# Power.net
KiCad netlist of a schematic drawn in Altium Designer
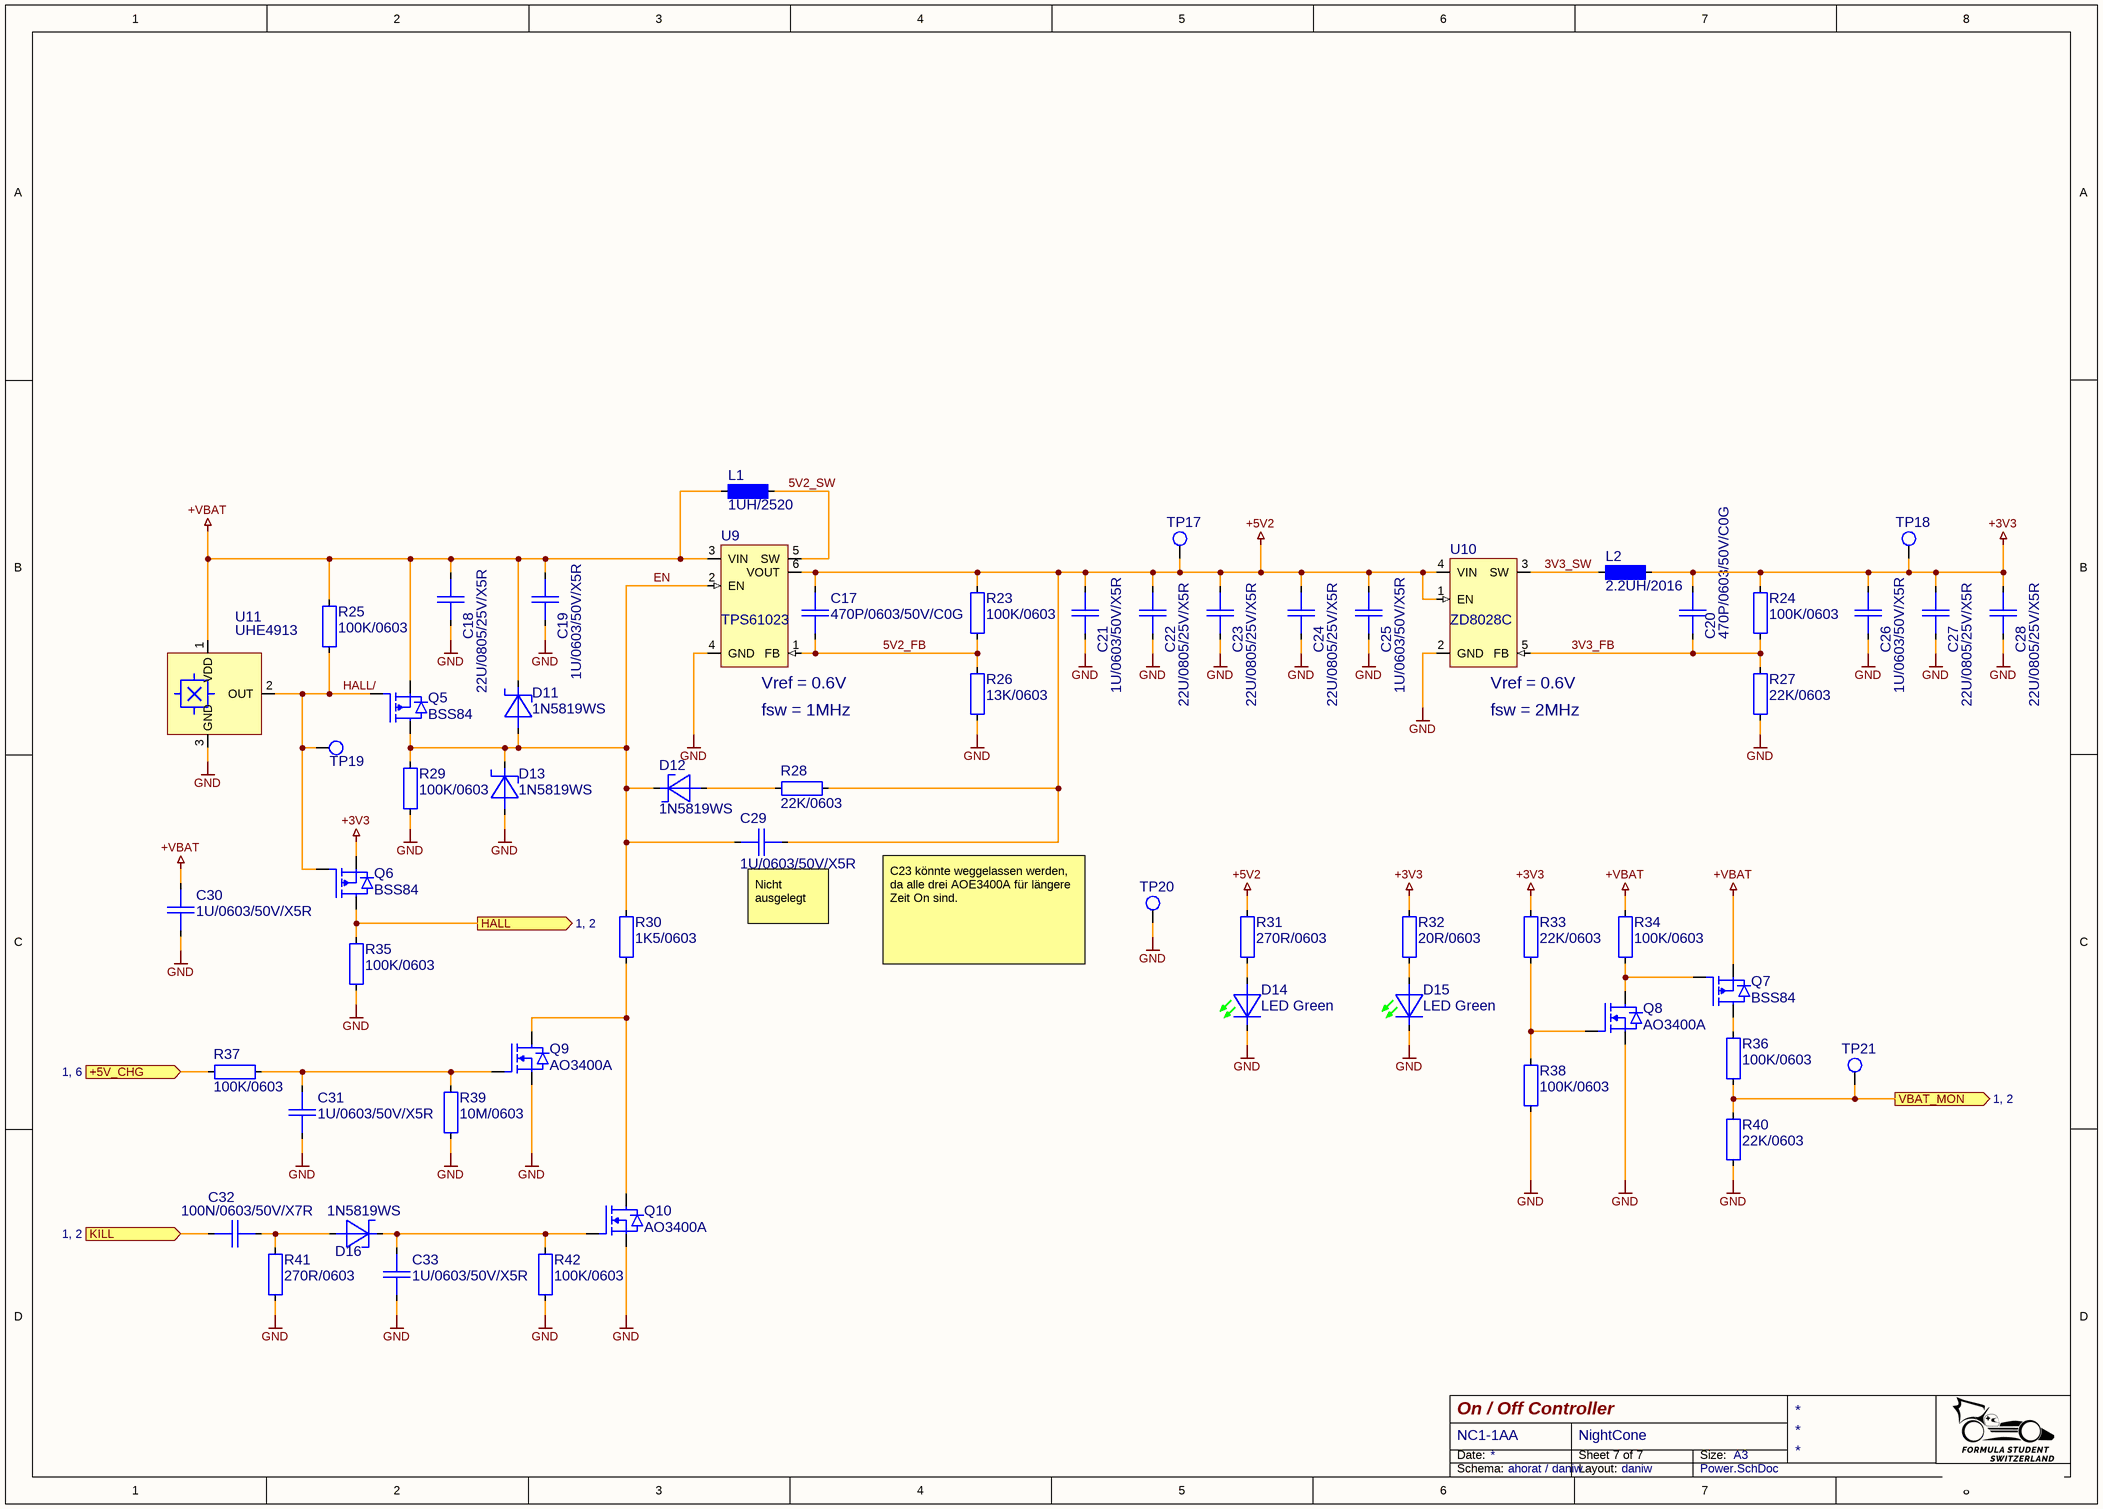
[diagram p0: Power.SchDoc]

(export (version "E")
  (design (tool "Eeschema 10.0.6"))
  (components
    (comp (ref "C17")
      (value "470P/0603/50V/C0G")
      (footprint "CAP0603_C0G")
      (description "CAP SM 0603 470pF 50V C0G")
      (fields (field (name "MANUFACTURER") "GENERIC"))
      (libsource (lib "daniw_altium_lib") (part "C"))
    )
    (comp (ref "C18")
      (value "22U/0805/25V/X5R")
      (footprint "CAP0805_X7R")
      (description "CAP SM 0805 22uF 25V X5R")
      (fields (field (name "MANUFACTURER") "GENERIC"))
      (libsource (lib "daniw_altium_lib") (part "C"))
    )
    (comp (ref "C19")
      (value "1U/0603/50V/X5R")
      (footprint "CAP0603_X7R")
      (description "CAP SM 0603 1.0uF 50V X5R")
      (fields (field (name "MANUFACTURER") "GENERIC"))
      (libsource (lib "daniw_altium_lib") (part "C"))
    )
    (comp (ref "C20")
      (value "470P/0603/50V/C0G")
      (footprint "CAP0603_C0G")
      (description "CAP SM 0603 470pF 50V C0G")
      (fields (field (name "MANUFACTURER") "GENERIC"))
      (libsource (lib "daniw_altium_lib") (part "C"))
    )
    (comp (ref "C21")
      (value "1U/0603/50V/X5R")
      (footprint "CAP0603_X7R")
      (description "CAP SM 0603 1.0uF 50V X5R")
      (fields (field (name "MANUFACTURER") "GENERIC"))
      (libsource (lib "daniw_altium_lib") (part "C"))
    )
    (comp (ref "C22")
      (value "22U/0805/25V/X5R")
      (footprint "CAP0805_X7R")
      (description "CAP SM 0805 22uF 25V X5R")
      (fields (field (name "MANUFACTURER") "GENERIC"))
      (libsource (lib "daniw_altium_lib") (part "C"))
    )
    (comp (ref "C23")
      (value "22U/0805/25V/X5R")
      (footprint "CAP0805_X7R")
      (description "CAP SM 0805 22uF 25V X5R")
      (fields (field (name "MANUFACTURER") "GENERIC"))
      (libsource (lib "daniw_altium_lib") (part "C"))
    )
    (comp (ref "C24")
      (value "22U/0805/25V/X5R")
      (footprint "CAP0805_X7R")
      (description "CAP SM 0805 22uF 25V X5R")
      (fields (field (name "MANUFACTURER") "GENERIC"))
      (libsource (lib "daniw_altium_lib") (part "C"))
    )
    (comp (ref "C25")
      (value "1U/0603/50V/X5R")
      (footprint "CAP0603_X7R")
      (description "CAP SM 0603 1.0uF 50V X5R")
      (fields (field (name "MANUFACTURER") "GENERIC"))
      (libsource (lib "daniw_altium_lib") (part "C"))
    )
    (comp (ref "C26")
      (value "1U/0603/50V/X5R")
      (footprint "CAP0603_X7R")
      (description "CAP SM 0603 1.0uF 50V X5R")
      (fields (field (name "MANUFACTURER") "GENERIC"))
      (libsource (lib "daniw_altium_lib") (part "C"))
    )
    (comp (ref "C27")
      (value "22U/0805/25V/X5R")
      (footprint "CAP0805_X7R")
      (description "CAP SM 0805 22uF 25V X5R")
      (fields (field (name "MANUFACTURER") "GENERIC"))
      (libsource (lib "daniw_altium_lib") (part "C"))
    )
    (comp (ref "C28")
      (value "22U/0805/25V/X5R")
      (footprint "CAP0805_X7R")
      (description "CAP SM 0805 22uF 25V X5R")
      (fields (field (name "MANUFACTURER") "GENERIC"))
      (libsource (lib "daniw_altium_lib") (part "C"))
    )
    (comp (ref "C29")
      (value "1U/0603/50V/X5R")
      (footprint "CAP0603_X7R")
      (description "CAP SM 0603 1.0uF 50V X5R")
      (fields (field (name "MANUFACTURER") "GENERIC"))
      (libsource (lib "daniw_altium_lib") (part "C"))
    )
    (comp (ref "C30")
      (value "1U/0603/50V/X5R")
      (footprint "CAP0603_X7R")
      (description "CAP SM 0603 1.0uF 50V X5R")
      (fields (field (name "MANUFACTURER") "GENERIC"))
      (libsource (lib "daniw_altium_lib") (part "C"))
    )
    (comp (ref "C31")
      (value "1U/0603/50V/X5R")
      (footprint "CAP0603_X7R")
      (description "CAP SM 0603 1.0uF 50V X5R")
      (fields (field (name "MANUFACTURER") "GENERIC"))
      (libsource (lib "daniw_altium_lib") (part "C"))
    )
    (comp (ref "C32")
      (value "100N/0603/50V/X7R")
      (footprint "CAP0603_X7R")
      (description "CAP SM 0603 100nF 50V X7R")
      (fields (field (name "MANUFACTURER") "GENERIC"))
      (libsource (lib "daniw_altium_lib") (part "C"))
    )
    (comp (ref "C33")
      (value "1U/0603/50V/X5R")
      (footprint "CAP0603_X7R")
      (description "CAP SM 0603 1.0uF 50V X5R")
      (fields (field (name "MANUFACTURER") "GENERIC"))
      (libsource (lib "daniw_altium_lib") (part "C"))
    )
    (comp (ref "D11")
      (value "1N5819WS")
      (footprint "SOD2513X100")
      (description "40V 600mV@1A 1A SOD-323 Schottky Barrier Diodes (SBD) ROHS")
      (fields (field (name "MANUFACTURER") "GENERIC"))
      (libsource (lib "daniw_altium_lib") (part "D_Schottky"))
    )
    (comp (ref "D12")
      (value "1N5819WS")
      (footprint "SOD2513X100")
      (description "40V 600mV@1A 1A SOD-323 Schottky Barrier Diodes (SBD) ROHS")
      (fields (field (name "MANUFACTURER") "GENERIC"))
      (libsource (lib "daniw_altium_lib") (part "D_Schottky"))
    )
    (comp (ref "D13")
      (value "1N5819WS")
      (footprint "SOD2513X100")
      (description "40V 600mV@1A 1A SOD-323 Schottky Barrier Diodes (SBD) ROHS")
      (fields (field (name "MANUFACTURER") "GENERIC"))
      (libsource (lib "daniw_altium_lib") (part "D_Schottky"))
    )
    (comp (ref "D14")
      (value "LED Green")
      (footprint "LED0805_GREEN")
      (description "Generic LED Green 0805")
      (fields (field (name "PART NUMBER") "LED Green 0805") (field (name "MANUFACTURER") "GENERIC"))
      (libsource (lib "daniw_altium_lib") (part "LED_GREEN"))
    )
    (comp (ref "D15")
      (value "LED Green")
      (footprint "LED0805_GREEN")
      (description "Generic LED Green 0805")
      (fields (field (name "PART NUMBER") "LED Green 0805") (field (name "MANUFACTURER") "GENERIC"))
      (libsource (lib "daniw_altium_lib") (part "LED_GREEN"))
    )
    (comp (ref "D16")
      (value "1N5819WS")
      (footprint "SOD2513X100")
      (description "40V 600mV@1A 1A SOD-323 Schottky Barrier Diodes (SBD) ROHS")
      (fields (field (name "MANUFACTURER") "GENERIC"))
      (libsource (lib "daniw_altium_lib") (part "D_Schottky"))
    )
    (comp (ref "L1")
      (value "1UH/2520")
      (footprint "INDM2520X10")
      (description "1UH 2520 Shielded Inductor SMD")
      (fields (field (name "MANUFACTURER") "GENERIC"))
      (libsource (lib "daniw_altium_lib") (part "L"))
    )
    (comp (ref "L2")
      (value "2.2UH/2016")
      (footprint "INDM2016X10")
      (description "2.2UH 2016 Shielded Inductor SMD")
      (fields (field (name "MANUFACTURER") "GENERIC"))
      (libsource (lib "daniw_altium_lib") (part "L"))
    )
    (comp (ref "Q5")
      (value "BSS84")
      (footprint "SOT2395P280X125-3-SE")
      (description "50V P-Channel MOSFET")
      (fields (field (name "MANUFACTURER") "GENERIC"))
      (libsource (lib "daniw_altium_lib") (part "MOSFET P_SOT23"))
    )
    (comp (ref "Q6")
      (value "BSS84")
      (footprint "SOT2395P280X125-3-SE")
      (description "50V P-Channel MOSFET")
      (fields (field (name "MANUFACTURER") "GENERIC"))
      (libsource (lib "daniw_altium_lib") (part "MOSFET P_SOT23"))
    )
    (comp (ref "Q7")
      (value "BSS84")
      (footprint "SOT2395P280X125-3-SE")
      (description "50V P-Channel MOSFET")
      (fields (field (name "MANUFACTURER") "GENERIC"))
      (libsource (lib "daniw_altium_lib") (part "MOSFET P_SOT23"))
    )
    (comp (ref "Q8")
      (value "AO3400A")
      (footprint "SOT2395P280X125-3-SE")
      (description "30V N-Channel MOSFET")
      (fields (field (name "MANUFACTURER") "Alpha & Omega Semiconductor"))
      (libsource (lib "daniw_altium_lib") (part "MOSFET N_SOT23"))
    )
    (comp (ref "Q9")
      (value "AO3400A")
      (footprint "SOT2395P280X125-3-SE")
      (description "30V N-Channel MOSFET")
      (fields (field (name "MANUFACTURER") "Alpha & Omega Semiconductor"))
      (libsource (lib "daniw_altium_lib") (part "MOSFET N_SOT23"))
    )
    (comp (ref "Q10")
      (value "AO3400A")
      (footprint "SOT2395P280X125-3-SE")
      (description "30V N-Channel MOSFET")
      (fields (field (name "MANUFACTURER") "Alpha & Omega Semiconductor"))
      (libsource (lib "daniw_altium_lib") (part "MOSFET N_SOT23"))
    )
    (comp (ref "R23")
      (value "100K/0603")
      (footprint "R0603-0.40-WW")
      (description "RES SM 0603 100K")
      (fields (field (name "MANUFACTURER") "GENERIC"))
      (libsource (lib "daniw_altium_lib") (part "R"))
    )
    (comp (ref "R24")
      (value "100K/0603")
      (footprint "R0603-0.40-WW")
      (description "RES SM 0603 100K")
      (fields (field (name "MANUFACTURER") "GENERIC"))
      (libsource (lib "daniw_altium_lib") (part "R"))
    )
    (comp (ref "R25")
      (value "100K/0603")
      (footprint "R0603-0.40-WW")
      (description "RES SM 0603 100K")
      (fields (field (name "MANUFACTURER") "GENERIC"))
      (libsource (lib "daniw_altium_lib") (part "R"))
    )
    (comp (ref "R26")
      (value "13K/0603")
      (footprint "R0603-0.40-WW")
      (description "RES SM 0603 13K")
      (fields (field (name "MANUFACTURER") "GENERIC"))
      (libsource (lib "daniw_altium_lib") (part "R"))
    )
    (comp (ref "R27")
      (value "22K/0603")
      (footprint "R0603-0.40-WW")
      (description "RES SM 0603 22K")
      (fields (field (name "MANUFACTURER") "GENERIC"))
      (libsource (lib "daniw_altium_lib") (part "R"))
    )
    (comp (ref "R28")
      (value "22K/0603")
      (footprint "R0603-0.40-WW")
      (description "RES SM 0603 22K")
      (fields (field (name "MANUFACTURER") "GENERIC"))
      (libsource (lib "daniw_altium_lib") (part "R"))
    )
    (comp (ref "R29")
      (value "100K/0603")
      (footprint "R0603-0.40-WW")
      (description "RES SM 0603 100K")
      (fields (field (name "MANUFACTURER") "GENERIC"))
      (libsource (lib "daniw_altium_lib") (part "R"))
    )
    (comp (ref "R30")
      (value "1K5/0603")
      (footprint "R0603-0.40-WW")
      (description "RES SM 0603 1K5")
      (fields (field (name "MANUFACTURER") "GENERIC"))
      (libsource (lib "daniw_altium_lib") (part "R"))
    )
    (comp (ref "R31")
      (value "270R/0603")
      (footprint "R0603-0.40-WW")
      (description "RES SM 0603 270R")
      (fields (field (name "MANUFACTURER") "GENERIC"))
      (libsource (lib "daniw_altium_lib") (part "R"))
    )
    (comp (ref "R32")
      (value "20R/0603")
      (footprint "R0603-0.40-WW")
      (description "RES SM 0603 20R")
      (fields (field (name "MANUFACTURER") "GENERIC"))
      (libsource (lib "daniw_altium_lib") (part "R"))
    )
    (comp (ref "R33")
      (value "22K/0603")
      (footprint "R0603-0.40-WW")
      (description "RES SM 0603 22K")
      (fields (field (name "MANUFACTURER") "GENERIC"))
      (libsource (lib "daniw_altium_lib") (part "R"))
    )
    (comp (ref "R34")
      (value "100K/0603")
      (footprint "R0603-0.40-WW")
      (description "RES SM 0603 100K")
      (fields (field (name "MANUFACTURER") "GENERIC"))
      (libsource (lib "daniw_altium_lib") (part "R"))
    )
    (comp (ref "R35")
      (value "100K/0603")
      (footprint "R0603-0.40-WW")
      (description "RES SM 0603 100K")
      (fields (field (name "MANUFACTURER") "GENERIC"))
      (libsource (lib "daniw_altium_lib") (part "R"))
    )
    (comp (ref "R36")
      (value "100K/0603")
      (footprint "R0603-0.40-WW")
      (description "RES SM 0603 100K")
      (fields (field (name "MANUFACTURER") "GENERIC"))
      (libsource (lib "daniw_altium_lib") (part "R"))
    )
    (comp (ref "R37")
      (value "100K/0603")
      (footprint "R0603-0.40-WW")
      (description "RES SM 0603 100K")
      (fields (field (name "MANUFACTURER") "GENERIC"))
      (libsource (lib "daniw_altium_lib") (part "R"))
    )
    (comp (ref "R38")
      (value "100K/0603")
      (footprint "R0603-0.40-WW")
      (description "RES SM 0603 100K")
      (fields (field (name "MANUFACTURER") "GENERIC"))
      (libsource (lib "daniw_altium_lib") (part "R"))
    )
    (comp (ref "R39")
      (value "10M/0603")
      (footprint "R0603-0.40-WW")
      (description "RES SM 0603 10M")
      (fields (field (name "MANUFACTURER") "GENERIC"))
      (libsource (lib "daniw_altium_lib") (part "R"))
    )
    (comp (ref "R40")
      (value "22K/0603")
      (footprint "R0603-0.40-WW")
      (description "RES SM 0603 22K")
      (fields (field (name "MANUFACTURER") "GENERIC"))
      (libsource (lib "daniw_altium_lib") (part "R"))
    )
    (comp (ref "R41")
      (value "270R/0603")
      (footprint "R0603-0.40-WW")
      (description "RES SM 0603 270R")
      (fields (field (name "MANUFACTURER") "GENERIC"))
      (libsource (lib "daniw_altium_lib") (part "R"))
    )
    (comp (ref "R42")
      (value "100K/0603")
      (footprint "R0603-0.40-WW")
      (description "RES SM 0603 100K")
      (fields (field (name "MANUFACTURER") "GENERIC"))
      (libsource (lib "daniw_altium_lib") (part "R"))
    )
    (comp (ref "TP17")
      (value "TP_THD_1.5/0.8")
      (footprint "TP_THD_1.5/0.8")
      (description "THT Test Point 1.5/0.8mm")
      (fields (field (name "MANUFACTURER") "NONE"))
      (libsource (lib "daniw_altium_lib") (part "Testpoint"))
    )
    (comp (ref "TP18")
      (value "TP_THD_1.5/0.8")
      (footprint "TP_THD_1.5/0.8")
      (description "THT Test Point 1.5/0.8mm")
      (fields (field (name "MANUFACTURER") "NONE"))
      (libsource (lib "daniw_altium_lib") (part "Testpoint"))
    )
    (comp (ref "TP19")
      (value "TP_THD_1.5/0.8")
      (footprint "TP_THD_1.5/0.8")
      (description "THT Test Point 1.5/0.8mm")
      (fields (field (name "MANUFACTURER") "NONE"))
      (libsource (lib "daniw_altium_lib") (part "Testpoint"))
    )
    (comp (ref "TP20")
      (value "TP_THD_1.5/0.8")
      (footprint "TP_THD_1.5/0.8")
      (description "THT Test Point 1.5/0.8mm")
      (fields (field (name "MANUFACTURER") "NONE"))
      (libsource (lib "daniw_altium_lib") (part "Testpoint"))
    )
    (comp (ref "TP21")
      (value "TP_THD_1.5/0.8")
      (footprint "TP_THD_1.5/0.8")
      (description "THT Test Point 1.5/0.8mm")
      (fields (field (name "MANUFACTURER") "NONE"))
      (libsource (lib "daniw_altium_lib") (part "Testpoint"))
    )
    (comp (ref "U9")
      (value "TPS61023")
      (footprint "SOT50P160X60-6-SE")
      (description "3.7-A Boost Converter with 0.5-V Ultra-low Input Voltage")
      (fields (field (name "MANUFACTURER") "Texas Instruments"))
      (libsource (lib "daniw_altium_lib") (part "TPS61023"))
    )
    (comp (ref "U10")
      (value "ZD8028C")
      (footprint "SOT2395P280X125-5-SW")
      (description "1.5A 2MHz 5.5V Synchronous Buck Converter")
      (fields (field (name "MANUFACTURER") "Zetta"))
      (libsource (lib "daniw_altium_lib") (part "ZD8028C"))
    )
    (comp (ref "U11")
      (value "UHE4913")
      (footprint "SOT2395P280X125-3-SE")
      (description "Ultra Low Power Hall Switch Open Drain")
      (fields (field (name "MANUFACTURER") "UTC(Unisonic Tech)"))
      (libsource (lib "daniw_altium_lib") (part "UHE4913"))
    )
  )
  (nets
    (net (code "1") (name "+3V3") (class "Default")
      (node (ref "C20") (pin "1") (pinfunction "1_1") (pintype "passive"))
      (node (ref "C26") (pin "2") (pinfunction "2_2") (pintype "passive"))
      (node (ref "C27") (pin "1") (pinfunction "1_1") (pintype "passive"))
      (node (ref "C28") (pin "1") (pinfunction "1_1") (pintype "passive"))
      (node (ref "L2") (pin "2") (pinfunction "2_2") (pintype "passive"))
      (node (ref "Q6") (pin "2") (pinfunction "SOURCE_2") (pintype "passive"))
      (node (ref "R24") (pin "1") (pinfunction "1_1") (pintype "passive"))
      (node (ref "R32") (pin "1") (pinfunction "1_1") (pintype "passive"))
      (node (ref "R33") (pin "1") (pinfunction "1_1") (pintype "passive"))
      (node (ref "TP18") (pin "1") (pinfunction "1_1") (pintype "passive"))
    )
    (net (code "2") (name "+5V2") (class "Default")
      (node (ref "C17") (pin "1") (pinfunction "1_1") (pintype "passive"))
      (node (ref "C21") (pin "2") (pinfunction "2_2") (pintype "passive"))
      (node (ref "C22") (pin "1") (pinfunction "1_1") (pintype "passive"))
      (node (ref "C23") (pin "1") (pinfunction "1_1") (pintype "passive"))
      (node (ref "C24") (pin "1") (pinfunction "1_1") (pintype "passive"))
      (node (ref "C25") (pin "2") (pinfunction "2_2") (pintype "passive"))
      (node (ref "C29") (pin "2") (pinfunction "2_2") (pintype "passive"))
      (node (ref "R23") (pin "1") (pinfunction "1_1") (pintype "passive"))
      (node (ref "R28") (pin "2") (pinfunction "2_2") (pintype "passive"))
      (node (ref "R31") (pin "1") (pinfunction "1_1") (pintype "passive"))
      (node (ref "TP17") (pin "1") (pinfunction "1_1") (pintype "passive"))
      (node (ref "U10") (pin "1") (pinfunction "EN_1") (pintype "input"))
      (node (ref "U10") (pin "4") (pinfunction "VIN_4") (pintype "passive"))
      (node (ref "U9") (pin "6") (pinfunction "VOUT_6") (pintype "passive"))
    )
    (net (code "3") (name "+VBAT") (class "Default")
      (node (ref "C18") (pin "1") (pinfunction "1_1") (pintype "passive"))
      (node (ref "C19") (pin "2") (pinfunction "2_2") (pintype "passive"))
      (node (ref "C30") (pin "1") (pinfunction "1_1") (pintype "passive"))
      (node (ref "D11") (pin "1") (pinfunction "1_1") (pintype "passive"))
      (node (ref "L1") (pin "1") (pinfunction "1_1") (pintype "passive"))
      (node (ref "Q5") (pin "2") (pinfunction "SOURCE_2") (pintype "passive"))
      (node (ref "Q7") (pin "2") (pinfunction "SOURCE_2") (pintype "passive"))
      (node (ref "R25") (pin "1") (pinfunction "1_1") (pintype "passive"))
      (node (ref "R34") (pin "1") (pinfunction "1_1") (pintype "passive"))
      (node (ref "U11") (pin "1") (pinfunction "VDD_1") (pintype "passive"))
      (node (ref "U9") (pin "3") (pinfunction "VIN_3") (pintype "passive"))
    )
    (net (code "4") (name "/+5V_CHG") (class "Default")
      (node (ref "R37") (pin "1") (pinfunction "1_1") (pintype "passive"))
    )
    (net (code "5") (name "/3V3_FB") (class "Default")
      (node (ref "C20") (pin "2") (pinfunction "2_2") (pintype "passive"))
      (node (ref "R24") (pin "2") (pinfunction "2_2") (pintype "passive"))
      (node (ref "R27") (pin "1") (pinfunction "1_1") (pintype "passive"))
      (node (ref "U10") (pin "5") (pinfunction "FB_5") (pintype "input"))
    )
    (net (code "6") (name "/3V3_SW") (class "Default")
      (node (ref "L2") (pin "1") (pinfunction "1_1") (pintype "passive"))
      (node (ref "U10") (pin "3") (pinfunction "SW_3") (pintype "passive"))
    )
    (net (code "7") (name "/5V2_FB") (class "Default")
      (node (ref "C17") (pin "2") (pinfunction "2_2") (pintype "passive"))
      (node (ref "R23") (pin "2") (pinfunction "2_2") (pintype "passive"))
      (node (ref "R26") (pin "2") (pinfunction "2_2") (pintype "passive"))
      (node (ref "U9") (pin "1") (pinfunction "FB_1") (pintype "input"))
    )
    (net (code "8") (name "/5V2_SW") (class "Default")
      (node (ref "L1") (pin "2") (pinfunction "2_2") (pintype "passive"))
      (node (ref "U9") (pin "5") (pinfunction "SW_5") (pintype "passive"))
    )
    (net (code "9") (name "/EN") (class "Default")
      (node (ref "C29") (pin "1") (pinfunction "1_1") (pintype "passive"))
      (node (ref "D11") (pin "2") (pinfunction "2_2") (pintype "passive"))
      (node (ref "D12") (pin "1") (pinfunction "1_1") (pintype "passive"))
      (node (ref "D13") (pin "1") (pinfunction "1_1") (pintype "passive"))
      (node (ref "Q5") (pin "3") (pinfunction "DRAIN_3") (pintype "passive"))
      (node (ref "R29") (pin "1") (pinfunction "1_1") (pintype "passive"))
      (node (ref "R30") (pin "1") (pinfunction "1_1") (pintype "passive"))
      (node (ref "U9") (pin "2") (pinfunction "EN_2") (pintype "input"))
    )
    (net (code "10") (name "/HALL") (class "Default")
      (node (ref "Q6") (pin "3") (pinfunction "DRAIN_3") (pintype "passive"))
      (node (ref "R35") (pin "1") (pinfunction "1_1") (pintype "passive"))
    )
    (net (code "11") (name "/HALL{slash}") (class "Default")
      (node (ref "Q5") (pin "1") (pinfunction "GATE_1") (pintype "passive"))
      (node (ref "Q6") (pin "1") (pinfunction "GATE_1") (pintype "passive"))
      (node (ref "R25") (pin "2") (pinfunction "2_2") (pintype "passive"))
      (node (ref "TP19") (pin "1") (pinfunction "1_1") (pintype "passive"))
      (node (ref "U11") (pin "2") (pinfunction "OUT_2") (pintype "open_collector"))
    )
    (net (code "12") (name "/KILL") (class "Default")
      (node (ref "C32") (pin "1") (pinfunction "1_1") (pintype "passive"))
    )
    (net (code "13") (name "/VBAT_MON") (class "Default")
      (node (ref "R36") (pin "2") (pinfunction "2_2") (pintype "passive"))
      (node (ref "R40") (pin "1") (pinfunction "1_1") (pintype "passive"))
      (node (ref "TP21") (pin "1") (pinfunction "1_1") (pintype "passive"))
    )
    (net (code "14") (name "GND") (class "Default")
      (node (ref "C18") (pin "2") (pinfunction "2_2") (pintype "passive"))
      (node (ref "C19") (pin "1") (pinfunction "1_1") (pintype "passive"))
      (node (ref "C21") (pin "1") (pinfunction "1_1") (pintype "passive"))
      (node (ref "C22") (pin "2") (pinfunction "2_2") (pintype "passive"))
      (node (ref "C23") (pin "2") (pinfunction "2_2") (pintype "passive"))
      (node (ref "C24") (pin "2") (pinfunction "2_2") (pintype "passive"))
      (node (ref "C25") (pin "1") (pinfunction "1_1") (pintype "passive"))
      (node (ref "C26") (pin "1") (pinfunction "1_1") (pintype "passive"))
      (node (ref "C27") (pin "2") (pinfunction "2_2") (pintype "passive"))
      (node (ref "C28") (pin "2") (pinfunction "2_2") (pintype "passive"))
      (node (ref "C30") (pin "2") (pinfunction "2_2") (pintype "passive"))
      (node (ref "C31") (pin "2") (pinfunction "2_2") (pintype "passive"))
      (node (ref "C33") (pin "2") (pinfunction "2_2") (pintype "passive"))
      (node (ref "D13") (pin "2") (pinfunction "2_2") (pintype "passive"))
      (node (ref "D14") (pin "1") (pinfunction "1_1") (pintype "passive"))
      (node (ref "D15") (pin "1") (pinfunction "1_1") (pintype "passive"))
      (node (ref "Q10") (pin "2") (pinfunction "SOURCE_2") (pintype "passive"))
      (node (ref "Q8") (pin "2") (pinfunction "SOURCE_2") (pintype "passive"))
      (node (ref "Q9") (pin "2") (pinfunction "SOURCE_2") (pintype "passive"))
      (node (ref "R26") (pin "1") (pinfunction "1_1") (pintype "passive"))
      (node (ref "R27") (pin "2") (pinfunction "2_2") (pintype "passive"))
      (node (ref "R29") (pin "2") (pinfunction "2_2") (pintype "passive"))
      (node (ref "R35") (pin "2") (pinfunction "2_2") (pintype "passive"))
      (node (ref "R38") (pin "2") (pinfunction "2_2") (pintype "passive"))
      (node (ref "R39") (pin "2") (pinfunction "2_2") (pintype "passive"))
      (node (ref "R40") (pin "2") (pinfunction "2_2") (pintype "passive"))
      (node (ref "R41") (pin "2") (pinfunction "2_2") (pintype "passive"))
      (node (ref "R42") (pin "2") (pinfunction "2_2") (pintype "passive"))
      (node (ref "TP20") (pin "1") (pinfunction "1_1") (pintype "passive"))
      (node (ref "U10") (pin "2") (pinfunction "GND_2") (pintype "passive"))
      (node (ref "U11") (pin "3") (pinfunction "GND_3") (pintype "passive"))
      (node (ref "U9") (pin "4") (pinfunction "GND_4") (pintype "passive"))
    )
    (net (code "15") (name "Net-(C32-Pad2)") (class "Default")
      (node (ref "C32") (pin "2") (pinfunction "2_2") (pintype "passive"))
      (node (ref "D16") (pin "2") (pinfunction "2_2") (pintype "passive"))
      (node (ref "R41") (pin "1") (pinfunction "1_1") (pintype "passive"))
    )
    (net (code "16") (name "Net-(D12-Pad2)") (class "Default")
      (node (ref "D12") (pin "2") (pinfunction "2_2") (pintype "passive"))
      (node (ref "R28") (pin "1") (pinfunction "1_1") (pintype "passive"))
    )
    (net (code "17") (name "Net-(D14-Pad2)") (class "Default")
      (node (ref "D14") (pin "2") (pinfunction "2_2") (pintype "passive"))
      (node (ref "R31") (pin "2") (pinfunction "2_2") (pintype "passive"))
    )
    (net (code "18") (name "Net-(D15-Pad2)") (class "Default")
      (node (ref "D15") (pin "2") (pinfunction "2_2") (pintype "passive"))
      (node (ref "R32") (pin "2") (pinfunction "2_2") (pintype "passive"))
    )
    (net (code "19") (name "Net-(Q7-DRAIN)") (class "Default")
      (node (ref "Q7") (pin "3") (pinfunction "DRAIN_3") (pintype "passive"))
      (node (ref "R36") (pin "1") (pinfunction "1_1") (pintype "passive"))
    )
    (net (code "20") (name "Net-(Q7-GATE)") (class "Default")
      (node (ref "Q7") (pin "1") (pinfunction "GATE_1") (pintype "passive"))
      (node (ref "Q8") (pin "3") (pinfunction "DRAIN_3") (pintype "passive"))
      (node (ref "R34") (pin "2") (pinfunction "2_2") (pintype "passive"))
    )
    (net (code "21") (name "Net-(Q8-GATE)") (class "Default")
      (node (ref "Q8") (pin "1") (pinfunction "GATE_1") (pintype "passive"))
      (node (ref "R33") (pin "2") (pinfunction "2_2") (pintype "passive"))
      (node (ref "R38") (pin "1") (pinfunction "1_1") (pintype "passive"))
    )
    (net (code "22") (name "Net-(Q9-GATE)") (class "Default")
      (node (ref "C31") (pin "1") (pinfunction "1_1") (pintype "passive"))
      (node (ref "Q9") (pin "1") (pinfunction "GATE_1") (pintype "passive"))
      (node (ref "R37") (pin "2") (pinfunction "2_2") (pintype "passive"))
      (node (ref "R39") (pin "1") (pinfunction "1_1") (pintype "passive"))
    )
    (net (code "23") (name "Net-(Q10-DRAIN)") (class "Default")
      (node (ref "Q10") (pin "3") (pinfunction "DRAIN_3") (pintype "passive"))
      (node (ref "Q9") (pin "3") (pinfunction "DRAIN_3") (pintype "passive"))
      (node (ref "R30") (pin "2") (pinfunction "2_2") (pintype "passive"))
    )
    (net (code "24") (name "Net-(Q10-GATE)") (class "Default")
      (node (ref "C33") (pin "1") (pinfunction "1_1") (pintype "passive"))
      (node (ref "D16") (pin "1") (pinfunction "1_1") (pintype "passive"))
      (node (ref "Q10") (pin "1") (pinfunction "GATE_1") (pintype "passive"))
      (node (ref "R42") (pin "1") (pinfunction "1_1") (pintype "passive"))
    )
  )
)
